# BlueSensor.net
KiCad netlist of a schematic drawn in EAGLE
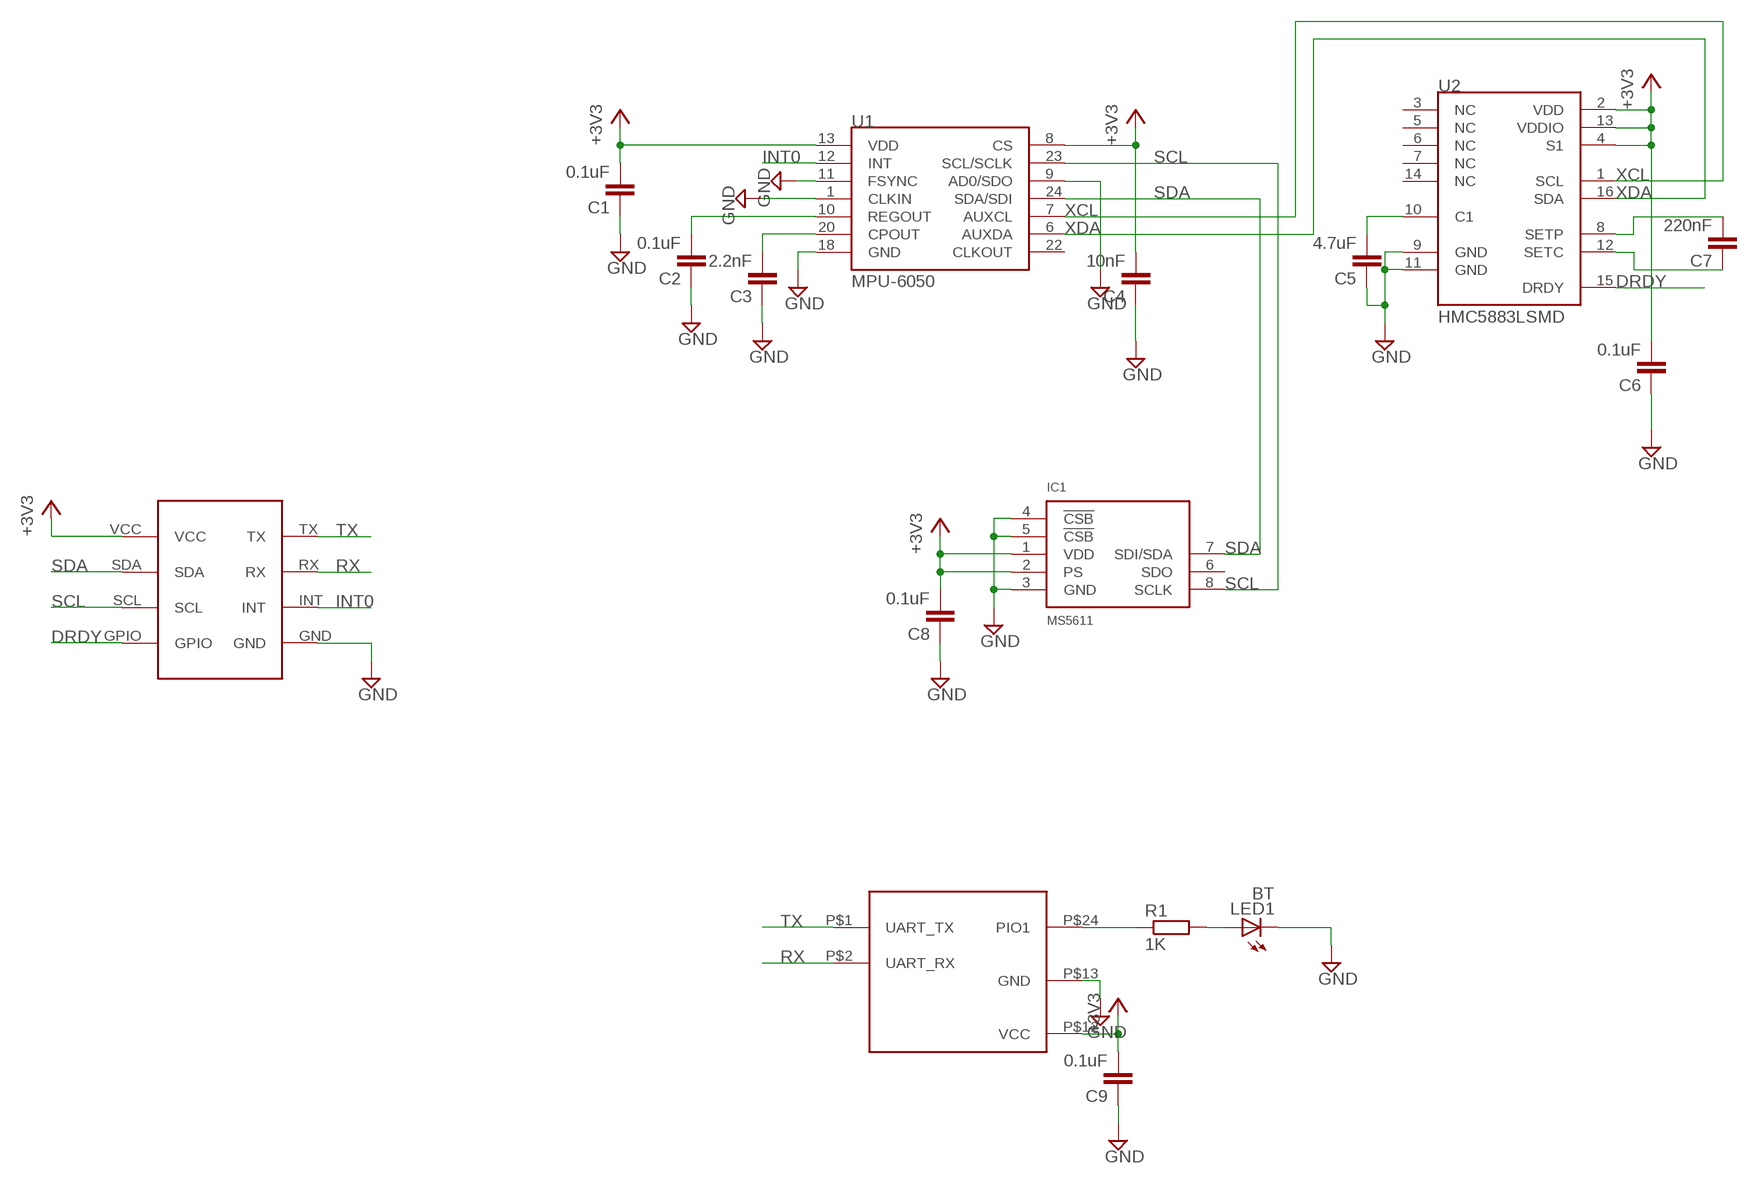
[diagram p0: schematic, sheet 1]

(export (version "E")
  (design (tool "Eeschema 10.0.6"))
  (components
    (comp (ref "C1")
      (value "0.1uF")
      (footprint "eagle-import:C0805")
      (libsource (lib "eagle-import") (part "C-EUC0805"))
    )
    (comp (ref "C2")
      (value "0.1uF")
      (footprint "eagle-import:C0805")
      (libsource (lib "eagle-import") (part "C-EUC0805"))
    )
    (comp (ref "C3")
      (value "2.2nF")
      (footprint "eagle-import:C0805")
      (libsource (lib "eagle-import") (part "C-EUC0805"))
    )
    (comp (ref "C4")
      (value "10nF")
      (footprint "eagle-import:C0805")
      (libsource (lib "eagle-import") (part "C-EUC0805"))
    )
    (comp (ref "C5")
      (value "4.7uF")
      (footprint "eagle-import:C0805")
      (libsource (lib "eagle-import") (part "C-EUC0805"))
    )
    (comp (ref "C6")
      (value "0.1uF")
      (footprint "eagle-import:C0805")
      (libsource (lib "eagle-import") (part "C-EUC0805"))
    )
    (comp (ref "C7")
      (value "220nF")
      (footprint "eagle-import:C0805")
      (libsource (lib "eagle-import") (part "C-EUC0805"))
    )
    (comp (ref "C8")
      (value "0.1uF")
      (footprint "eagle-import:C0805")
      (libsource (lib "eagle-import") (part "C-EUC0805"))
    )
    (comp (ref "C9")
      (value "0.1uF")
      (footprint "eagle-import:C0805")
      (libsource (lib "eagle-import") (part "C-EUC0805"))
    )
    (comp (ref "IC1")
      (value "MS5611")
      (footprint "eagle-import:QFN-MS5611")
      (libsource (lib "eagle-import") (part "MS5611"))
    )
    (comp (ref "LED1")
      (value "BT")
      (footprint "eagle-import:CHIPLED_0805")
      (libsource (lib "eagle-import") (part "LEDCHIPLED_0805"))
    )
    (comp (ref "R1")
      (value "1K")
      (footprint "eagle-import:R0805")
      (libsource (lib "eagle-import") (part "R-EU_R0805"))
    )
    (comp (ref "U$1")
      (value "BLUESIMPLEHC-07")
      (footprint "eagle-import:HC-07-SIMPLE")
      (libsource (lib "eagle-import") (part "BLUESIMPLEHC-07"))
    )
    (comp (ref "U$2")
      (value "BLUESENSORBOARD")
      (footprint "eagle-import:BLUESENSOR-BOARD")
      (libsource (lib "eagle-import") (part "BLUESENSORBOARD"))
    )
    (comp (ref "U1")
      (value "MPU-6050")
      (footprint "eagle-import:QFN-24-TESTING")
      (libsource (lib "eagle-import") (part "MPU-6000QFN-24"))
    )
    (comp (ref "U2")
      (value "HMC5883LSMD")
      (footprint "eagle-import:16LPCC")
      (libsource (lib "eagle-import") (part "HMC5883LSMD"))
    )
  )
  (nets
    (net (code "1") (name "+3V3") (class "Default")
      (node (ref "C1") (pin "2") (pinfunction "2_2") (pintype "passive"))
      (node (ref "C4") (pin "2") (pinfunction "2_2") (pintype "passive"))
      (node (ref "C6") (pin "2") (pinfunction "2_2") (pintype "passive"))
      (node (ref "C8") (pin "2") (pinfunction "2_2") (pintype "passive"))
      (node (ref "C9") (pin "2") (pinfunction "2_2") (pintype "passive"))
      (node (ref "IC1") (pin "1") (pinfunction "VDD_1") (pintype "bidirectional"))
      (node (ref "IC1") (pin "2") (pinfunction "PS_2") (pintype "bidirectional"))
      (node (ref "U$1") (pin "P$12") (pinfunction "VCC_P$12") (pintype "bidirectional"))
      (node (ref "U$2") (pin "VCC") (pinfunction "VCC_VCC") (pintype "bidirectional"))
      (node (ref "U1") (pin "13") (pinfunction "VDD_13") (pintype "bidirectional"))
      (node (ref "U1") (pin "8") (pinfunction "CS_8") (pintype "bidirectional"))
      (node (ref "U2") (pin "13") (pinfunction "VDDIO_13") (pintype "bidirectional"))
      (node (ref "U2") (pin "2") (pinfunction "VDD_2") (pintype "bidirectional"))
      (node (ref "U2") (pin "4") (pinfunction "S1_4") (pintype "bidirectional"))
    )
    (net (code "2") (name "/DRDY") (class "Default")
      (node (ref "U$2") (pin "GPIO") (pinfunction "GPIO_GPIO") (pintype "bidirectional"))
      (node (ref "U2") (pin "15") (pinfunction "DRDY_15") (pintype "bidirectional"))
    )
    (net (code "3") (name "/INT0") (class "Default")
      (node (ref "U$2") (pin "INT") (pinfunction "INT_INT") (pintype "bidirectional"))
      (node (ref "U1") (pin "12") (pinfunction "INT_12") (pintype "bidirectional"))
    )
    (net (code "4") (name "/RX") (class "Default")
      (node (ref "U$1") (pin "P$2") (pinfunction "UART_RX_P$2") (pintype "bidirectional"))
      (node (ref "U$2") (pin "RX") (pinfunction "RX_RX") (pintype "bidirectional"))
    )
    (net (code "5") (name "/SCL") (class "Default")
      (node (ref "IC1") (pin "8") (pinfunction "SCLK_8") (pintype "bidirectional"))
      (node (ref "U$2") (pin "SCL") (pinfunction "SCL_SCL") (pintype "bidirectional"))
      (node (ref "U1") (pin "23") (pinfunction "SCL/SCLK_23") (pintype "bidirectional"))
    )
    (net (code "6") (name "/SDA") (class "Default")
      (node (ref "IC1") (pin "7") (pinfunction "SDI/SDA_7") (pintype "bidirectional"))
      (node (ref "U$2") (pin "SDA") (pinfunction "SDA_SDA") (pintype "bidirectional"))
      (node (ref "U1") (pin "24") (pinfunction "SDA/SDI_24") (pintype "bidirectional"))
    )
    (net (code "7") (name "/TX") (class "Default")
      (node (ref "U$1") (pin "P$1") (pinfunction "UART_TX_P$1") (pintype "bidirectional"))
      (node (ref "U$2") (pin "TX") (pinfunction "TX_TX") (pintype "bidirectional"))
    )
    (net (code "8") (name "/XCL") (class "Default")
      (node (ref "U1") (pin "7") (pinfunction "AUXCL_7") (pintype "bidirectional"))
      (node (ref "U2") (pin "1") (pinfunction "SCL_1") (pintype "bidirectional"))
    )
    (net (code "9") (name "/XDA") (class "Default")
      (node (ref "U1") (pin "6") (pinfunction "AUXDA_6") (pintype "bidirectional"))
      (node (ref "U2") (pin "16") (pinfunction "SDA_16") (pintype "bidirectional"))
    )
    (net (code "10") (name "GND") (class "Default")
      (node (ref "C1") (pin "1") (pinfunction "1_1") (pintype "passive"))
      (node (ref "C2") (pin "1") (pinfunction "1_1") (pintype "passive"))
      (node (ref "C3") (pin "1") (pinfunction "1_1") (pintype "passive"))
      (node (ref "C4") (pin "1") (pinfunction "1_1") (pintype "passive"))
      (node (ref "C5") (pin "1") (pinfunction "1_1") (pintype "passive"))
      (node (ref "C6") (pin "1") (pinfunction "1_1") (pintype "passive"))
      (node (ref "C8") (pin "1") (pinfunction "1_1") (pintype "passive"))
      (node (ref "C9") (pin "1") (pinfunction "1_1") (pintype "passive"))
      (node (ref "IC1") (pin "3") (pinfunction "GND_3") (pintype "bidirectional"))
      (node (ref "IC1") (pin "4") (pinfunction "~{CSB}_4") (pintype "bidirectional"))
      (node (ref "IC1") (pin "5") (pinfunction "~{CSB}_5") (pintype "bidirectional"))
      (node (ref "LED1") (pin "C") (pinfunction "C_C") (pintype "passive"))
      (node (ref "U$1") (pin "P$13") (pinfunction "GND_P$13") (pintype "bidirectional"))
      (node (ref "U$2") (pin "GND") (pinfunction "GND_GND") (pintype "bidirectional"))
      (node (ref "U1") (pin "1") (pinfunction "CLKIN_1") (pintype "bidirectional"))
      (node (ref "U1") (pin "11") (pinfunction "FSYNC_11") (pintype "bidirectional"))
      (node (ref "U1") (pin "18") (pinfunction "GND_18") (pintype "bidirectional"))
      (node (ref "U1") (pin "9") (pinfunction "AD0/SDO_9") (pintype "bidirectional"))
      (node (ref "U2") (pin "11") (pinfunction "GND_11") (pintype "bidirectional"))
      (node (ref "U2") (pin "9") (pinfunction "GND_9") (pintype "bidirectional"))
    )
    (net (code "11") (name "Net-(LED1-PadA)") (class "Default")
      (node (ref "LED1") (pin "A") (pinfunction "A_A") (pintype "passive"))
      (node (ref "R1") (pin "2") (pinfunction "2_2") (pintype "passive"))
    )
    (net (code "12") (name "Net-(U$1-PIO1)") (class "Default")
      (node (ref "R1") (pin "1") (pinfunction "1_1") (pintype "passive"))
      (node (ref "U$1") (pin "P$24") (pinfunction "PIO1_P$24") (pintype "bidirectional"))
    )
    (net (code "13") (name "Net-(U1-CPOUT)") (class "Default")
      (node (ref "C3") (pin "2") (pinfunction "2_2") (pintype "passive"))
      (node (ref "U1") (pin "20") (pinfunction "CPOUT_20") (pintype "bidirectional"))
    )
    (net (code "14") (name "Net-(U1-REGOUT)") (class "Default")
      (node (ref "C2") (pin "2") (pinfunction "2_2") (pintype "passive"))
      (node (ref "U1") (pin "10") (pinfunction "REGOUT_10") (pintype "bidirectional"))
    )
    (net (code "15") (name "Net-(U2-C1)") (class "Default")
      (node (ref "C5") (pin "2") (pinfunction "2_2") (pintype "passive"))
      (node (ref "U2") (pin "10") (pinfunction "C1_10") (pintype "bidirectional"))
    )
    (net (code "16") (name "Net-(U2-SETC)") (class "Default")
      (node (ref "C7") (pin "1") (pinfunction "1_1") (pintype "passive"))
      (node (ref "U2") (pin "12") (pinfunction "SETC_12") (pintype "bidirectional"))
    )
    (net (code "17") (name "Net-(U2-SETP)") (class "Default")
      (node (ref "C7") (pin "2") (pinfunction "2_2") (pintype "passive"))
      (node (ref "U2") (pin "8") (pinfunction "SETP_8") (pintype "bidirectional"))
    )
    (net (code "18") (name "unconnected-(IC1-SDO-Pad6)") (class "Default")
      (node (ref "IC1") (pin "6") (pinfunction "SDO_6") (pintype "bidirectional"))
    )
    (net (code "19") (name "unconnected-(U1-CLKOUT-Pad22)") (class "Default")
      (node (ref "U1") (pin "22") (pinfunction "CLKOUT_22") (pintype "bidirectional"))
    )
    (net (code "20") (name "unconnected-(U2-NC-Pad3)") (class "Default")
      (node (ref "U2") (pin "3") (pinfunction "NC_3") (pintype "bidirectional"))
    )
    (net (code "21") (name "unconnected-(U2-NC-Pad5)") (class "Default")
      (node (ref "U2") (pin "5") (pinfunction "NC_5") (pintype "bidirectional"))
    )
    (net (code "22") (name "unconnected-(U2-NC-Pad6)") (class "Default")
      (node (ref "U2") (pin "6") (pinfunction "NC_6") (pintype "bidirectional"))
    )
    (net (code "23") (name "unconnected-(U2-NC-Pad7)") (class "Default")
      (node (ref "U2") (pin "7") (pinfunction "NC_7") (pintype "bidirectional"))
    )
    (net (code "24") (name "unconnected-(U2-NC-Pad14)") (class "Default")
      (node (ref "U2") (pin "14") (pinfunction "NC_14") (pintype "bidirectional"))
    )
  )
)
